# i2c-devices.net
KiCad netlist of a schematic drawn in EAGLE
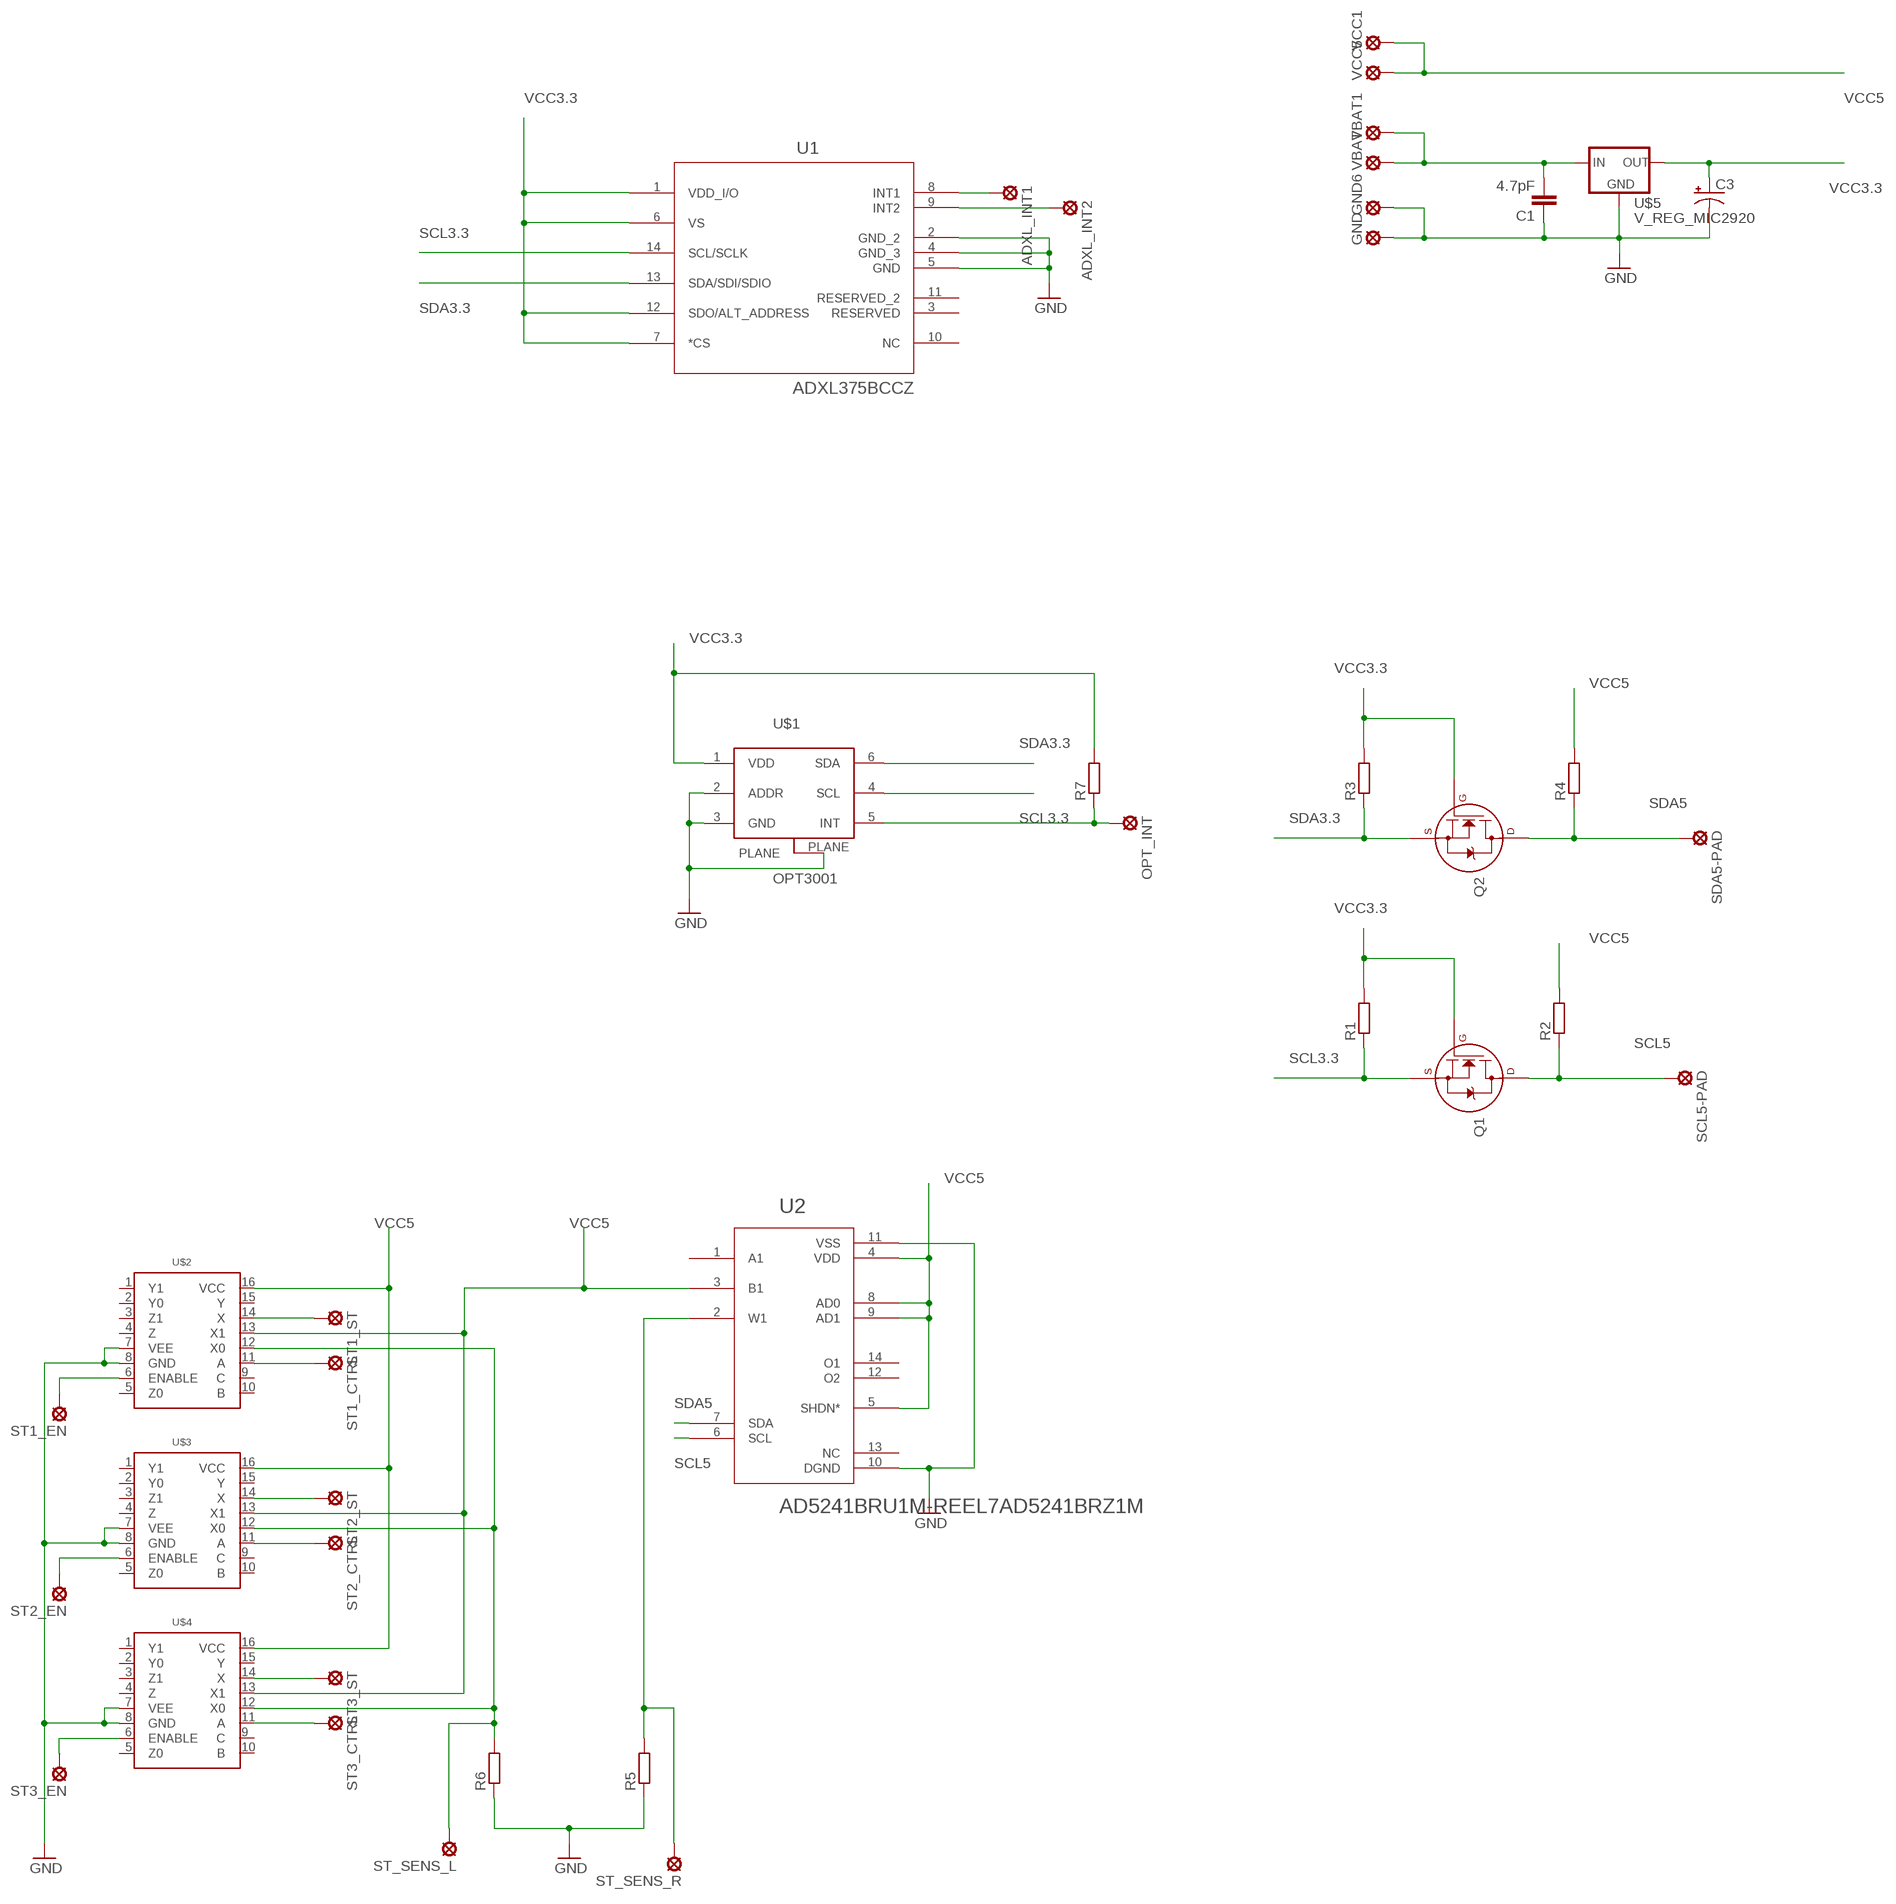
[diagram p0: schematic, sheet 1]

(export (version "E")
  (design (tool "Eeschema 10.0.6"))
  (components
    (comp (ref "ADXL_INT1")
      (value "LSP10")
      (footprint "eagle-import:LSP10")
      (libsource (lib "eagle-import") (part "LSP10"))
    )
    (comp (ref "ADXL_INT2")
      (value "LSP10")
      (footprint "eagle-import:LSP10")
      (libsource (lib "eagle-import") (part "LSP10"))
    )
    (comp (ref "C1")
      (value "4.7pF")
      (footprint "eagle-import:C0603")
      (libsource (lib "eagle-import") (part "C-EUC0603"))
    )
    (comp (ref "C3")
      (value "CAP_POL3528")
      (footprint "eagle-import:EIA3528")
      (libsource (lib "eagle-import") (part "CAP_POL3528"))
    )
    (comp (ref "GND")
      (value "LSP10")
      (footprint "eagle-import:LSP10")
      (libsource (lib "eagle-import") (part "LSP10"))
    )
    (comp (ref "GND6")
      (value "LSP10")
      (footprint "eagle-import:LSP10")
      (libsource (lib "eagle-import") (part "LSP10"))
    )
    (comp (ref "OPT_INT")
      (value "LSP10")
      (footprint "eagle-import:LSP10")
      (libsource (lib "eagle-import") (part "LSP10"))
    )
    (comp (ref "Q1")
      (value "2N7002_SOT23")
      (footprint "eagle-import:SOT-23")
      (libsource (lib "eagle-import") (part "2N700_SOT232"))
    )
    (comp (ref "Q2")
      (value "2N7002_SOT23")
      (footprint "eagle-import:SOT-23")
      (libsource (lib "eagle-import") (part "2N700_SOT232"))
    )
    (comp (ref "R1")
      (value "R-EU_R0805")
      (footprint "eagle-import:R0805")
      (libsource (lib "eagle-import") (part "R-EU_R0805"))
    )
    (comp (ref "R2")
      (value "R-EU_R0805")
      (footprint "eagle-import:R0805")
      (libsource (lib "eagle-import") (part "R-EU_R0805"))
    )
    (comp (ref "R3")
      (value "R-EU_R0805")
      (footprint "eagle-import:R0805")
      (libsource (lib "eagle-import") (part "R-EU_R0805"))
    )
    (comp (ref "R4")
      (value "R-EU_R0805")
      (footprint "eagle-import:R0805")
      (libsource (lib "eagle-import") (part "R-EU_R0805"))
    )
    (comp (ref "R5")
      (value "R-EU_R0805")
      (footprint "eagle-import:R0805")
      (libsource (lib "eagle-import") (part "R-EU_R0805"))
    )
    (comp (ref "R6")
      (value "R-EU_R0805")
      (footprint "eagle-import:R0805")
      (libsource (lib "eagle-import") (part "R-EU_R0805"))
    )
    (comp (ref "R7")
      (value "R-EU_R0805")
      (footprint "eagle-import:R0805")
      (libsource (lib "eagle-import") (part "R-EU_R0805"))
    )
    (comp (ref "SCL5-PAD")
      (value "LSP10")
      (footprint "eagle-import:LSP10")
      (libsource (lib "eagle-import") (part "LSP10"))
    )
    (comp (ref "SDA5-PAD")
      (value "LSP10")
      (footprint "eagle-import:LSP10")
      (libsource (lib "eagle-import") (part "LSP10"))
    )
    (comp (ref "ST1_CTRL")
      (value "LSP10")
      (footprint "eagle-import:LSP10")
      (libsource (lib "eagle-import") (part "LSP10"))
    )
    (comp (ref "ST1_EN")
      (value "LSP10")
      (footprint "eagle-import:LSP10")
      (libsource (lib "eagle-import") (part "LSP10"))
    )
    (comp (ref "ST1_ST")
      (value "LSP10")
      (footprint "eagle-import:LSP10")
      (libsource (lib "eagle-import") (part "LSP10"))
    )
    (comp (ref "ST2_CTRL")
      (value "LSP10")
      (footprint "eagle-import:LSP10")
      (libsource (lib "eagle-import") (part "LSP10"))
    )
    (comp (ref "ST2_EN")
      (value "LSP10")
      (footprint "eagle-import:LSP10")
      (libsource (lib "eagle-import") (part "LSP10"))
    )
    (comp (ref "ST2_ST")
      (value "LSP10")
      (footprint "eagle-import:LSP10")
      (libsource (lib "eagle-import") (part "LSP10"))
    )
    (comp (ref "ST3_CTRL")
      (value "LSP10")
      (footprint "eagle-import:LSP10")
      (libsource (lib "eagle-import") (part "LSP10"))
    )
    (comp (ref "ST3_EN")
      (value "LSP10")
      (footprint "eagle-import:LSP10")
      (libsource (lib "eagle-import") (part "LSP10"))
    )
    (comp (ref "ST3_ST")
      (value "LSP10")
      (footprint "eagle-import:LSP10")
      (libsource (lib "eagle-import") (part "LSP10"))
    )
    (comp (ref "ST_SENS_L")
      (value "LSP10")
      (footprint "eagle-import:LSP10")
      (libsource (lib "eagle-import") (part "LSP10"))
    )
    (comp (ref "ST_SENS_R")
      (value "LSP10")
      (footprint "eagle-import:LSP10")
      (libsource (lib "eagle-import") (part "LSP10"))
    )
    (comp (ref "U$1")
      (value "OPT3001")
      (footprint "eagle-import:OPT3001")
      (libsource (lib "eagle-import") (part "OPT3001"))
    )
    (comp (ref "U$2")
      (value "MC74HC4051AMC74HC4051AG")
      (footprint "eagle-import:SOIC-16")
      (libsource (lib "eagle-import") (part "MC74HC4051AMC74HC4051AG"))
    )
    (comp (ref "U$3")
      (value "MC74HC4051AMC74HC4051AG")
      (footprint "eagle-import:SOIC-16")
      (libsource (lib "eagle-import") (part "MC74HC4051AMC74HC4051AG"))
    )
    (comp (ref "U$4")
      (value "MC74HC4051AMC74HC4051AG")
      (footprint "eagle-import:SOIC-16")
      (libsource (lib "eagle-import") (part "MC74HC4051AMC74HC4051AG"))
    )
    (comp (ref "U$5")
      (value "V_REG_MIC2920")
      (footprint "eagle-import:SOT223")
      (libsource (lib "eagle-import") (part "V_REG_MIC2920"))
    )
    (comp (ref "U1")
      (value "ADXL375BCCZ")
      (footprint "eagle-import:LGA_CC-14-1")
      (libsource (lib "eagle-import") (part "ADXL375BCCZ"))
    )
    (comp (ref "U2")
      (value "AD5241BRU1M-REEL7AD5241BRZ1M")
      (footprint "eagle-import:SOIC-14")
      (libsource (lib "eagle-import") (part "AD5241BRU1M-REEL7AD5241BRZ1M"))
    )
    (comp (ref "VBAT")
      (value "LSP10")
      (footprint "eagle-import:LSP10")
      (libsource (lib "eagle-import") (part "LSP10"))
    )
    (comp (ref "VBAT1")
      (value "LSP10")
      (footprint "eagle-import:LSP10")
      (libsource (lib "eagle-import") (part "LSP10"))
    )
    (comp (ref "VCC1")
      (value "LSP10")
      (footprint "eagle-import:LSP10")
      (libsource (lib "eagle-import") (part "LSP10"))
    )
    (comp (ref "VCC5")
      (value "LSP10")
      (footprint "eagle-import:LSP10")
      (libsource (lib "eagle-import") (part "LSP10"))
    )
  )
  (nets
    (net (code "1") (name "/SCL3.3") (class "Default")
      (node (ref "Q1") (pin "2") (pinfunction "S_2") (pintype "bidirectional"))
      (node (ref "R1") (pin "1") (pinfunction "1_1") (pintype "passive"))
      (node (ref "U$1") (pin "4") (pinfunction "SCL_4") (pintype "bidirectional"))
      (node (ref "U1") (pin "14") (pinfunction "SCL/SCLK_14") (pintype "passive"))
    )
    (net (code "2") (name "/SCL5") (class "Default")
      (node (ref "Q1") (pin "3") (pinfunction "D_3") (pintype "bidirectional"))
      (node (ref "R2") (pin "1") (pinfunction "1_1") (pintype "passive"))
      (node (ref "SCL5-PAD") (pin "MP") (pinfunction "MP_MP") (pintype "passive"))
      (node (ref "U2") (pin "6") (pinfunction "SCL_6") (pintype "passive"))
    )
    (net (code "3") (name "/SDA3.3") (class "Default")
      (node (ref "Q2") (pin "2") (pinfunction "S_2") (pintype "bidirectional"))
      (node (ref "R3") (pin "1") (pinfunction "1_1") (pintype "passive"))
      (node (ref "U$1") (pin "6") (pinfunction "SDA_6") (pintype "bidirectional"))
      (node (ref "U1") (pin "13") (pinfunction "SDA/SDI/SDIO_13") (pintype "passive"))
    )
    (net (code "4") (name "/SDA5") (class "Default")
      (node (ref "Q2") (pin "3") (pinfunction "D_3") (pintype "bidirectional"))
      (node (ref "R4") (pin "1") (pinfunction "1_1") (pintype "passive"))
      (node (ref "SDA5-PAD") (pin "MP") (pinfunction "MP_MP") (pintype "passive"))
      (node (ref "U2") (pin "7") (pinfunction "SDA_7") (pintype "passive"))
    )
    (net (code "5") (name "/VCC3.3") (class "Default")
      (node (ref "C3") (pin "A") (pinfunction "+_A") (pintype "passive"))
      (node (ref "Q1") (pin "1") (pinfunction "G_1") (pintype "tri_state"))
      (node (ref "Q2") (pin "1") (pinfunction "G_1") (pintype "tri_state"))
      (node (ref "R1") (pin "2") (pinfunction "2_2") (pintype "passive"))
      (node (ref "R3") (pin "2") (pinfunction "2_2") (pintype "passive"))
      (node (ref "R7") (pin "2") (pinfunction "2_2") (pintype "passive"))
      (node (ref "U$1") (pin "1") (pinfunction "VDD_1") (pintype "power_in"))
      (node (ref "U$5") (pin "3") (pinfunction "OUT_3") (pintype "passive"))
      (node (ref "U1") (pin "1") (pinfunction "VDD_I/O_1") (pintype "passive"))
      (node (ref "U1") (pin "12") (pinfunction "SDO/ALT_ADDRESS_12") (pintype "passive"))
      (node (ref "U1") (pin "6") (pinfunction "VS_6") (pintype "passive"))
      (node (ref "U1") (pin "7") (pinfunction "*CS_7") (pintype "passive"))
    )
    (net (code "6") (name "/VCC5") (class "Default")
      (node (ref "R2") (pin "2") (pinfunction "2_2") (pintype "passive"))
      (node (ref "R4") (pin "2") (pinfunction "2_2") (pintype "passive"))
      (node (ref "U$2") (pin "13") (pinfunction "X1_13") (pintype "bidirectional"))
      (node (ref "U$2") (pin "16") (pinfunction "VCC_16") (pintype "bidirectional"))
      (node (ref "U$3") (pin "13") (pinfunction "X1_13") (pintype "bidirectional"))
      (node (ref "U$3") (pin "16") (pinfunction "VCC_16") (pintype "bidirectional"))
      (node (ref "U$4") (pin "13") (pinfunction "X1_13") (pintype "bidirectional"))
      (node (ref "U$4") (pin "16") (pinfunction "VCC_16") (pintype "bidirectional"))
      (node (ref "U2") (pin "3") (pinfunction "B1_3") (pintype "passive"))
      (node (ref "U2") (pin "4") (pinfunction "VDD_4") (pintype "power_in"))
      (node (ref "U2") (pin "5") (pinfunction "SHDN*_5") (pintype "passive"))
      (node (ref "U2") (pin "8") (pinfunction "AD0_8") (pintype "passive"))
      (node (ref "U2") (pin "9") (pinfunction "AD1_9") (pintype "passive"))
      (node (ref "VCC1") (pin "MP") (pinfunction "MP_MP") (pintype "passive"))
      (node (ref "VCC5") (pin "MP") (pinfunction "MP_MP") (pintype "passive"))
    )
    (net (code "7") (name "GND") (class "Default")
      (node (ref "C1") (pin "1") (pinfunction "1_1") (pintype "passive"))
      (node (ref "C3") (pin "C") (pinfunction "-_C") (pintype "passive"))
      (node (ref "GND") (pin "MP") (pinfunction "MP_MP") (pintype "passive"))
      (node (ref "GND6") (pin "MP") (pinfunction "MP_MP") (pintype "passive"))
      (node (ref "R5") (pin "1") (pinfunction "1_1") (pintype "passive"))
      (node (ref "R6") (pin "1") (pinfunction "1_1") (pintype "passive"))
      (node (ref "U$1") (pin "2") (pinfunction "ADDR_2") (pintype "bidirectional"))
      (node (ref "U$1") (pin "3") (pinfunction "GND_3") (pintype "power_in"))
      (node (ref "U$1") (pin "PLANE") (pinfunction "PLANE_PLANE") (pintype "bidirectional"))
      (node (ref "U$2") (pin "7") (pinfunction "VEE_7") (pintype "bidirectional"))
      (node (ref "U$2") (pin "8") (pinfunction "GND_8") (pintype "bidirectional"))
      (node (ref "U$3") (pin "7") (pinfunction "VEE_7") (pintype "bidirectional"))
      (node (ref "U$3") (pin "8") (pinfunction "GND_8") (pintype "bidirectional"))
      (node (ref "U$4") (pin "7") (pinfunction "VEE_7") (pintype "bidirectional"))
      (node (ref "U$4") (pin "8") (pinfunction "GND_8") (pintype "bidirectional"))
      (node (ref "U$5") (pin "2") (pinfunction "GND_2") (pintype "input"))
      (node (ref "U1") (pin "2") (pinfunction "GND_2_2") (pintype "passive"))
      (node (ref "U1") (pin "4") (pinfunction "GND_3_4") (pintype "passive"))
      (node (ref "U1") (pin "5") (pinfunction "GND_5") (pintype "passive"))
      (node (ref "U2") (pin "10") (pinfunction "DGND_10") (pintype "passive"))
      (node (ref "U2") (pin "11") (pinfunction "VSS_11") (pintype "power_in"))
    )
    (net (code "8") (name "Net-(U$1-INT)") (class "Default")
      (node (ref "OPT_INT") (pin "MP") (pinfunction "MP_MP") (pintype "passive"))
      (node (ref "R7") (pin "1") (pinfunction "1_1") (pintype "passive"))
      (node (ref "U$1") (pin "5") (pinfunction "INT_5") (pintype "output"))
    )
    (net (code "9") (name "Net-(U$2-A)") (class "Default")
      (node (ref "ST1_CTRL") (pin "MP") (pinfunction "MP_MP") (pintype "passive"))
      (node (ref "U$2") (pin "11") (pinfunction "A_11") (pintype "bidirectional"))
    )
    (net (code "10") (name "Net-(U$2-ENABLE)") (class "Default")
      (node (ref "ST1_EN") (pin "MP") (pinfunction "MP_MP") (pintype "passive"))
      (node (ref "U$2") (pin "6") (pinfunction "ENABLE_6") (pintype "bidirectional"))
    )
    (net (code "11") (name "Net-(U$2-X)") (class "Default")
      (node (ref "ST1_ST") (pin "MP") (pinfunction "MP_MP") (pintype "passive"))
      (node (ref "U$2") (pin "14") (pinfunction "X_14") (pintype "bidirectional"))
    )
    (net (code "12") (name "Net-(U$2-X0)") (class "Default")
      (node (ref "R6") (pin "2") (pinfunction "2_2") (pintype "passive"))
      (node (ref "ST_SENS_L") (pin "MP") (pinfunction "MP_MP") (pintype "passive"))
      (node (ref "U$2") (pin "12") (pinfunction "X0_12") (pintype "bidirectional"))
      (node (ref "U$3") (pin "12") (pinfunction "X0_12") (pintype "bidirectional"))
      (node (ref "U$4") (pin "12") (pinfunction "X0_12") (pintype "bidirectional"))
    )
    (net (code "13") (name "Net-(U$3-A)") (class "Default")
      (node (ref "ST2_CTRL") (pin "MP") (pinfunction "MP_MP") (pintype "passive"))
      (node (ref "U$3") (pin "11") (pinfunction "A_11") (pintype "bidirectional"))
    )
    (net (code "14") (name "Net-(U$3-ENABLE)") (class "Default")
      (node (ref "ST2_EN") (pin "MP") (pinfunction "MP_MP") (pintype "passive"))
      (node (ref "U$3") (pin "6") (pinfunction "ENABLE_6") (pintype "bidirectional"))
    )
    (net (code "15") (name "Net-(U$3-X)") (class "Default")
      (node (ref "ST2_ST") (pin "MP") (pinfunction "MP_MP") (pintype "passive"))
      (node (ref "U$3") (pin "14") (pinfunction "X_14") (pintype "bidirectional"))
    )
    (net (code "16") (name "Net-(U$4-A)") (class "Default")
      (node (ref "ST3_CTRL") (pin "MP") (pinfunction "MP_MP") (pintype "passive"))
      (node (ref "U$4") (pin "11") (pinfunction "A_11") (pintype "bidirectional"))
    )
    (net (code "17") (name "Net-(U$4-ENABLE)") (class "Default")
      (node (ref "ST3_EN") (pin "MP") (pinfunction "MP_MP") (pintype "passive"))
      (node (ref "U$4") (pin "6") (pinfunction "ENABLE_6") (pintype "bidirectional"))
    )
    (net (code "18") (name "Net-(U$4-X)") (class "Default")
      (node (ref "ST3_ST") (pin "MP") (pinfunction "MP_MP") (pintype "passive"))
      (node (ref "U$4") (pin "14") (pinfunction "X_14") (pintype "bidirectional"))
    )
    (net (code "19") (name "Net-(U$5-IN)") (class "Default")
      (node (ref "C1") (pin "2") (pinfunction "2_2") (pintype "passive"))
      (node (ref "U$5") (pin "1") (pinfunction "IN_1") (pintype "input"))
      (node (ref "VBAT") (pin "MP") (pinfunction "MP_MP") (pintype "passive"))
      (node (ref "VBAT1") (pin "MP") (pinfunction "MP_MP") (pintype "passive"))
    )
    (net (code "20") (name "Net-(U1-INT1)") (class "Default")
      (node (ref "ADXL_INT1") (pin "MP") (pinfunction "MP_MP") (pintype "passive"))
      (node (ref "U1") (pin "8") (pinfunction "INT1_8") (pintype "passive"))
    )
    (net (code "21") (name "Net-(U1-INT2)") (class "Default")
      (node (ref "ADXL_INT2") (pin "MP") (pinfunction "MP_MP") (pintype "passive"))
      (node (ref "U1") (pin "9") (pinfunction "INT2_9") (pintype "passive"))
    )
    (net (code "22") (name "Net-(U2-W1)") (class "Default")
      (node (ref "R5") (pin "2") (pinfunction "2_2") (pintype "passive"))
      (node (ref "ST_SENS_R") (pin "MP") (pinfunction "MP_MP") (pintype "passive"))
      (node (ref "U2") (pin "2") (pinfunction "W1_2") (pintype "passive"))
    )
    (net (code "23") (name "unconnected-(U$2-B-Pad10)") (class "Default")
      (node (ref "U$2") (pin "10") (pinfunction "B_10") (pintype "bidirectional"))
    )
    (net (code "24") (name "unconnected-(U$2-C-Pad9)") (class "Default")
      (node (ref "U$2") (pin "9") (pinfunction "C_9") (pintype "bidirectional"))
    )
    (net (code "25") (name "unconnected-(U$2-Y-Pad15)") (class "Default")
      (node (ref "U$2") (pin "15") (pinfunction "Y_15") (pintype "bidirectional"))
    )
    (net (code "26") (name "unconnected-(U$2-Y0-Pad2)") (class "Default")
      (node (ref "U$2") (pin "2") (pinfunction "Y0_2") (pintype "bidirectional"))
    )
    (net (code "27") (name "unconnected-(U$2-Y1-Pad1)") (class "Default")
      (node (ref "U$2") (pin "1") (pinfunction "Y1_1") (pintype "bidirectional"))
    )
    (net (code "28") (name "unconnected-(U$2-Z-Pad4)") (class "Default")
      (node (ref "U$2") (pin "4") (pinfunction "Z_4") (pintype "bidirectional"))
    )
    (net (code "29") (name "unconnected-(U$2-Z0-Pad5)") (class "Default")
      (node (ref "U$2") (pin "5") (pinfunction "Z0_5") (pintype "bidirectional"))
    )
    (net (code "30") (name "unconnected-(U$2-Z1-Pad3)") (class "Default")
      (node (ref "U$2") (pin "3") (pinfunction "Z1_3") (pintype "bidirectional"))
    )
    (net (code "31") (name "unconnected-(U$3-B-Pad10)") (class "Default")
      (node (ref "U$3") (pin "10") (pinfunction "B_10") (pintype "bidirectional"))
    )
    (net (code "32") (name "unconnected-(U$3-C-Pad9)") (class "Default")
      (node (ref "U$3") (pin "9") (pinfunction "C_9") (pintype "bidirectional"))
    )
    (net (code "33") (name "unconnected-(U$3-Y-Pad15)") (class "Default")
      (node (ref "U$3") (pin "15") (pinfunction "Y_15") (pintype "bidirectional"))
    )
    (net (code "34") (name "unconnected-(U$3-Y0-Pad2)") (class "Default")
      (node (ref "U$3") (pin "2") (pinfunction "Y0_2") (pintype "bidirectional"))
    )
    (net (code "35") (name "unconnected-(U$3-Y1-Pad1)") (class "Default")
      (node (ref "U$3") (pin "1") (pinfunction "Y1_1") (pintype "bidirectional"))
    )
    (net (code "36") (name "unconnected-(U$3-Z-Pad4)") (class "Default")
      (node (ref "U$3") (pin "4") (pinfunction "Z_4") (pintype "bidirectional"))
    )
    (net (code "37") (name "unconnected-(U$3-Z0-Pad5)") (class "Default")
      (node (ref "U$3") (pin "5") (pinfunction "Z0_5") (pintype "bidirectional"))
    )
    (net (code "38") (name "unconnected-(U$3-Z1-Pad3)") (class "Default")
      (node (ref "U$3") (pin "3") (pinfunction "Z1_3") (pintype "bidirectional"))
    )
    (net (code "39") (name "unconnected-(U$4-B-Pad10)") (class "Default")
      (node (ref "U$4") (pin "10") (pinfunction "B_10") (pintype "bidirectional"))
    )
    (net (code "40") (name "unconnected-(U$4-C-Pad9)") (class "Default")
      (node (ref "U$4") (pin "9") (pinfunction "C_9") (pintype "bidirectional"))
    )
    (net (code "41") (name "unconnected-(U$4-Y-Pad15)") (class "Default")
      (node (ref "U$4") (pin "15") (pinfunction "Y_15") (pintype "bidirectional"))
    )
    (net (code "42") (name "unconnected-(U$4-Y0-Pad2)") (class "Default")
      (node (ref "U$4") (pin "2") (pinfunction "Y0_2") (pintype "bidirectional"))
    )
    (net (code "43") (name "unconnected-(U$4-Y1-Pad1)") (class "Default")
      (node (ref "U$4") (pin "1") (pinfunction "Y1_1") (pintype "bidirectional"))
    )
    (net (code "44") (name "unconnected-(U$4-Z-Pad4)") (class "Default")
      (node (ref "U$4") (pin "4") (pinfunction "Z_4") (pintype "bidirectional"))
    )
    (net (code "45") (name "unconnected-(U$4-Z0-Pad5)") (class "Default")
      (node (ref "U$4") (pin "5") (pinfunction "Z0_5") (pintype "bidirectional"))
    )
    (net (code "46") (name "unconnected-(U$4-Z1-Pad3)") (class "Default")
      (node (ref "U$4") (pin "3") (pinfunction "Z1_3") (pintype "bidirectional"))
    )
    (net (code "47") (name "unconnected-(U1-NC-Pad10)") (class "Default")
      (node (ref "U1") (pin "10") (pinfunction "NC_10") (pintype "passive"))
    )
    (net (code "48") (name "unconnected-(U1-RESERVED-Pad3)") (class "Default")
      (node (ref "U1") (pin "3") (pinfunction "RESERVED_3") (pintype "passive"))
    )
    (net (code "49") (name "unconnected-(U1-RESERVED_2-Pad11)") (class "Default")
      (node (ref "U1") (pin "11") (pinfunction "RESERVED_2_11") (pintype "passive"))
    )
    (net (code "50") (name "unconnected-(U2-A1-Pad1)") (class "Default")
      (node (ref "U2") (pin "1") (pinfunction "A1_1") (pintype "passive"))
    )
    (net (code "51") (name "unconnected-(U2-NC-Pad13)") (class "Default")
      (node (ref "U2") (pin "13") (pinfunction "NC_13") (pintype "passive"))
    )
    (net (code "52") (name "unconnected-(U2-O1-Pad14)") (class "Default")
      (node (ref "U2") (pin "14") (pinfunction "O1_14") (pintype "passive"))
    )
    (net (code "53") (name "unconnected-(U2-O2-Pad12)") (class "Default")
      (node (ref "U2") (pin "12") (pinfunction "O2_12") (pintype "passive"))
    )
  )
)
